# SolarPwrOption_short.net
KiCad netlist of a schematic drawn in EAGLE
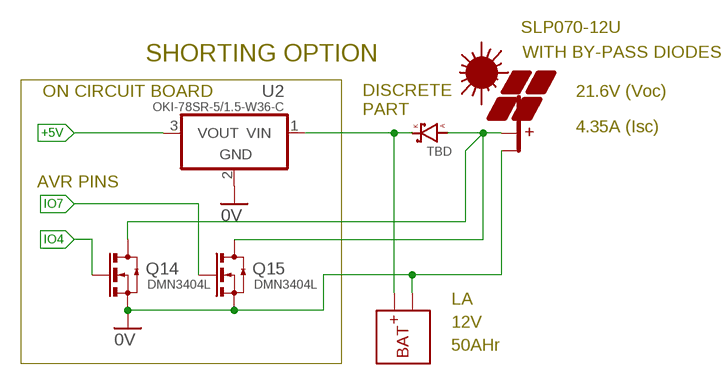
[diagram p0: schematic, sheet 1]

(export (version "E")
  (design (tool "Eeschema 10.0.6"))
  (components
    (comp (ref "PV1")
      (value "PV")
      (footprint "eagle-import:NA-30")
      (libsource (lib "eagle-import") (part "PV"))
    )
    (comp (ref "Q14")
      (value "DMN3404L")
      (footprint "eagle-import:DPAK")
      (libsource (lib "eagle-import") (part "N-CH?DPAK"))
    )
    (comp (ref "Q15")
      (value "DMN3404L")
      (footprint "eagle-import:DPAK")
      (libsource (lib "eagle-import") (part "N-CH?DPAK"))
    )
    (comp (ref "U$10")
      (value "BAT")
      (footprint "eagle-import:NA-30")
      (libsource (lib "eagle-import") (part "BAT"))
    )
    (comp (ref "U2")
      (value "OKI-78SR-5/1.5-W36-C")
      (footprint "eagle-import:OKI-78SR-H")
      (libsource (lib "eagle-import") (part "OKI-78SR-H"))
    )
    (comp (ref "_D1")
      (value "TBD")
      (footprint "eagle-import:SMB")
      (libsource (lib "eagle-import") (part "DSMB"))
    )
  )
  (nets
    (net (code "1") (name "+5V") (class "Default")
      (node (ref "U2") (pin "3") (pinfunction "VOUT_3") (pintype "passive"))
    )
    (net (code "2") (name "0V") (class "Default")
      (node (ref "PV1") (pin "2") (pinfunction "-PV_2") (pintype "bidirectional"))
      (node (ref "Q14") (pin "3") (pinfunction "S_3") (pintype "passive"))
      (node (ref "Q15") (pin "3") (pinfunction "S_3") (pintype "passive"))
      (node (ref "U$10") (pin "2") (pinfunction "-BAT_2") (pintype "bidirectional"))
      (node (ref "U2") (pin "2") (pinfunction "GND_2") (pintype "passive"))
    )
    (net (code "3") (name "IO4") (class "Default")
      (node (ref "Q14") (pin "1") (pinfunction "G_1") (pintype "passive"))
    )
    (net (code "4") (name "IO7") (class "Default")
      (node (ref "Q15") (pin "1") (pinfunction "G_1") (pintype "passive"))
    )
    (net (code "5") (name "Net-(PV1-+PV)") (class "Default")
      (node (ref "PV1") (pin "1") (pinfunction "+PV_1") (pintype "bidirectional"))
      (node (ref "Q14") (pin "SINK") (pinfunction "D_SINK") (pintype "passive"))
      (node (ref "Q15") (pin "SINK") (pinfunction "D_SINK") (pintype "passive"))
      (node (ref "_D1") (pin "A") (pinfunction "A_A") (pintype "passive"))
    )
    (net (code "6") (name "Net-(U$10-+BAT)") (class "Default")
      (node (ref "U$10") (pin "1") (pinfunction "+BAT_1") (pintype "bidirectional"))
      (node (ref "U2") (pin "1") (pinfunction "VIN_1") (pintype "passive"))
      (node (ref "_D1") (pin "K") (pinfunction "K_K") (pintype "passive"))
    )
  )
)
